# 1_Power.net
KiCad netlist of a schematic drawn in Altium Designer
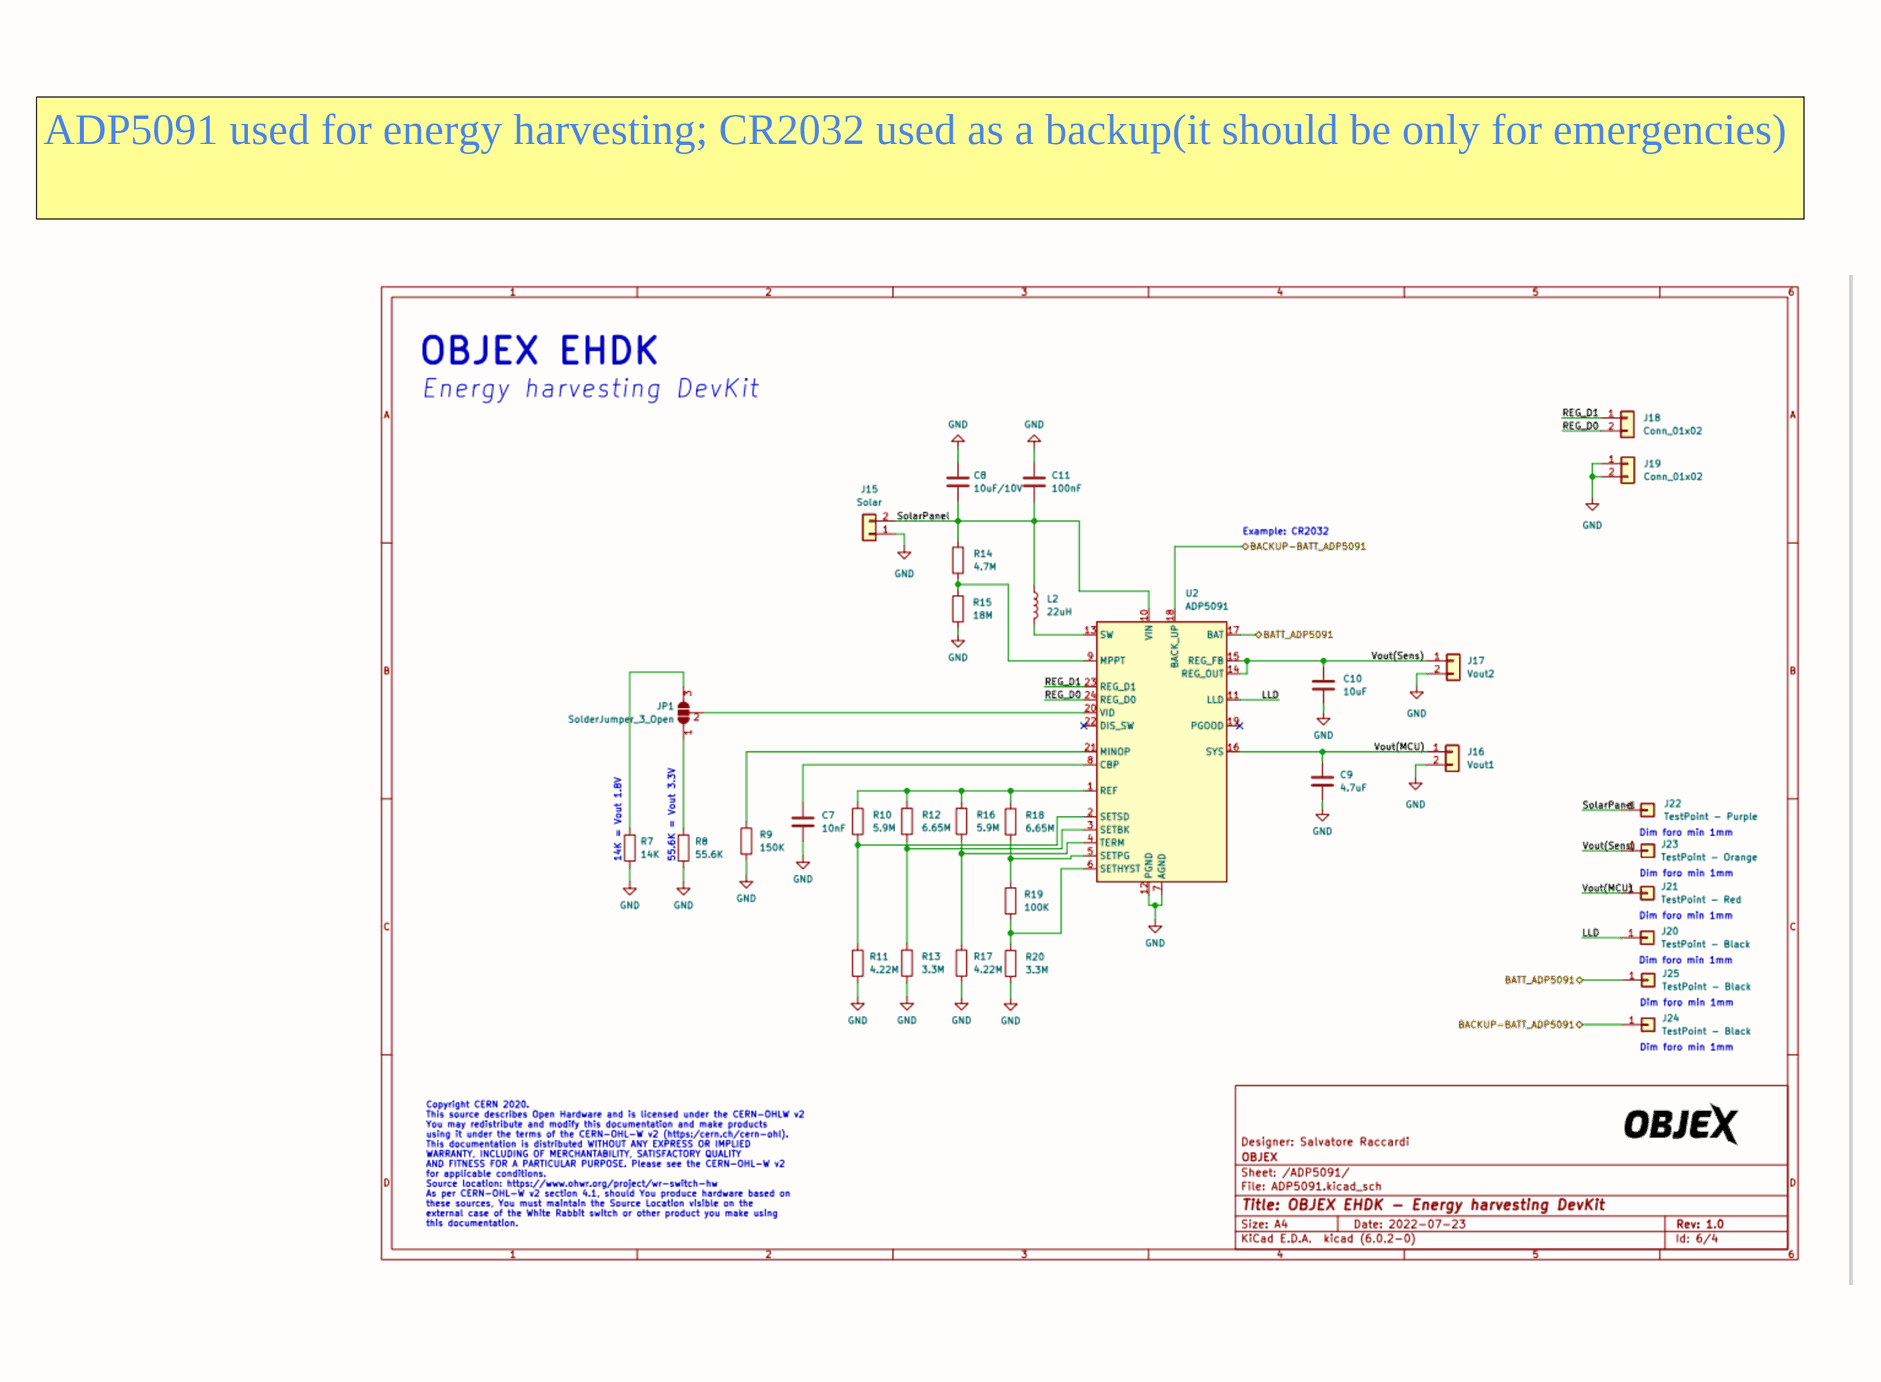
[diagram p0: 1_Power.SchDoc, left]
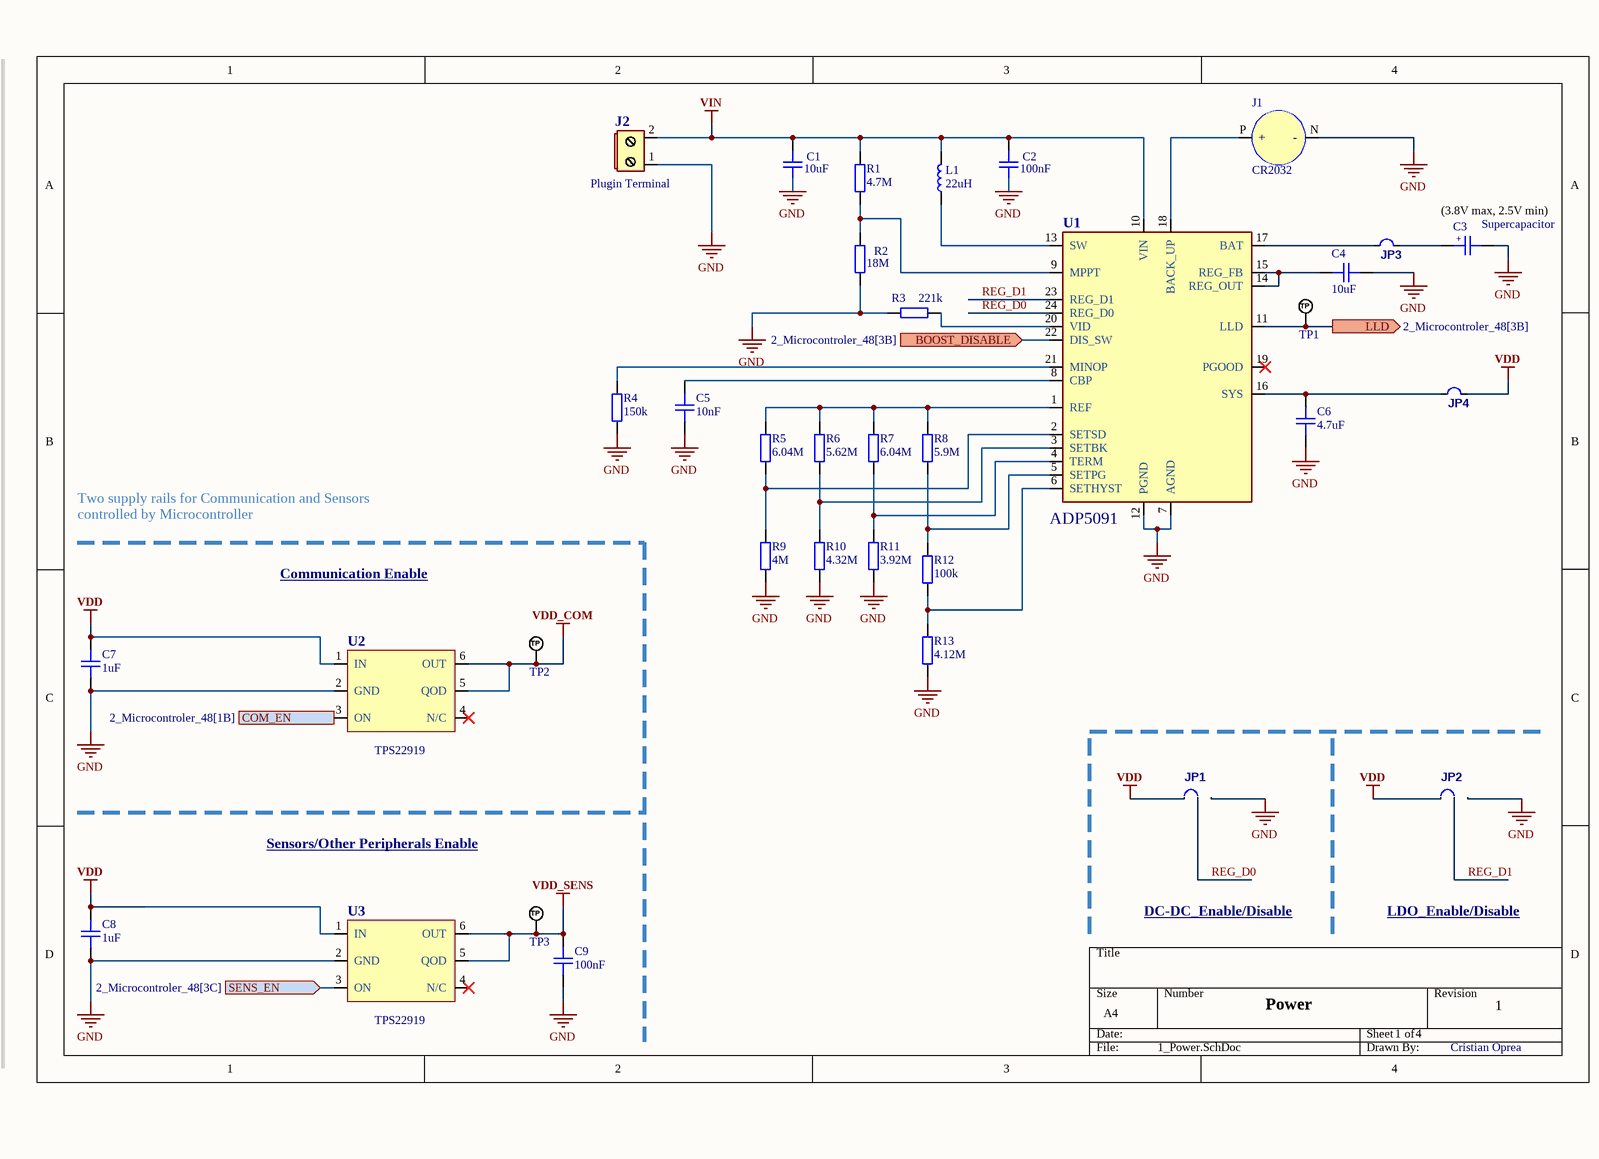
[diagram p1: 1_Power.SchDoc, middle]
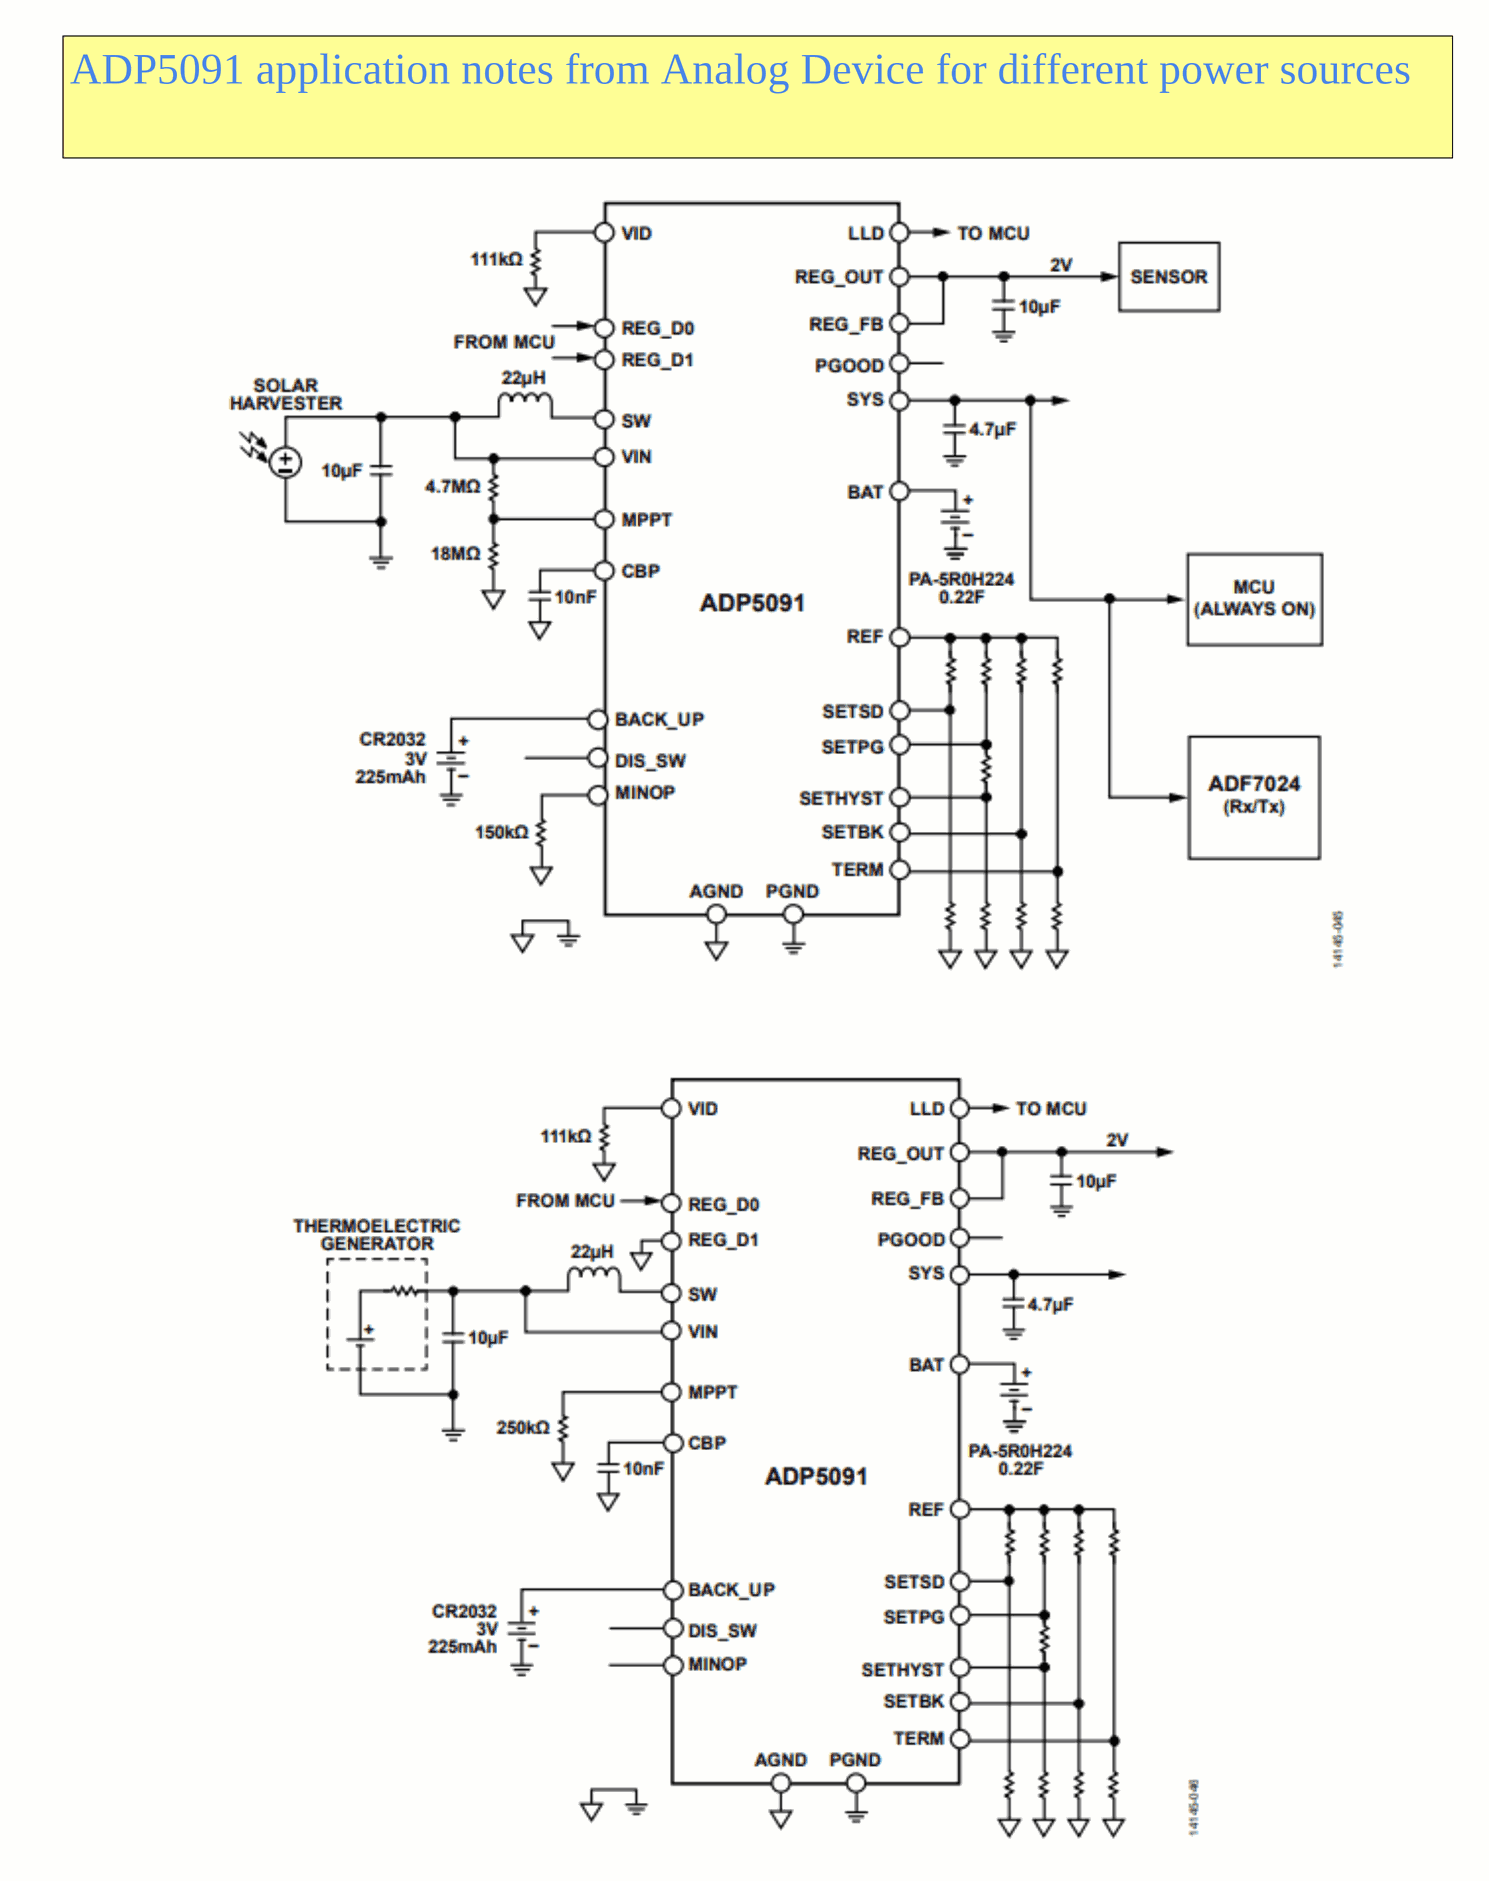
[diagram p2: 1_Power.SchDoc, right]

(export (version "E")
  (design (tool "Eeschema 10.0.6"))
  (components
    (comp (ref "C1")
      (value "10uF")
      (footprint "C0603")
      (description "Capacitor SMD 0603")
      (libsource (lib "Schlib_H2") (part "CAP_0603"))
    )
    (comp (ref "C2")
      (value "100nF")
      (footprint "C0603")
      (description "Capacitor SMD 0603")
      (libsource (lib "Schlib_H2") (part "CAP_0603"))
    )
    (comp (ref "C3")
      (value "Supercapacitor")
      (footprint "CAP_POL_8x16x3.5")
      (libsource (lib "Schlib_H2") (part "Supercapacitor"))
    )
    (comp (ref "C4")
      (value "10uF")
      (footprint "C0805")
      (description "Capacitor SMD 0805")
      (libsource (lib "Schlib_H2") (part "CAP_0805"))
    )
    (comp (ref "C5")
      (value "10nF")
      (footprint "C0603")
      (description "Capacitor SMD 0603")
      (libsource (lib "Schlib_H2") (part "CAP_0603"))
    )
    (comp (ref "C6")
      (value "4.7uF")
      (footprint "C0603")
      (description "Capacitor SMD 0603")
      (libsource (lib "Schlib_H2") (part "CAP_0603"))
    )
    (comp (ref "C7")
      (value "1uF")
      (footprint "C0603")
      (description "Capacitor SMD 0603")
      (libsource (lib "Schlib_H2") (part "CAP_0603"))
    )
    (comp (ref "C8")
      (value "1uF")
      (footprint "C0603")
      (description "Capacitor SMD 0603")
      (libsource (lib "Schlib_H2") (part "CAP_0603"))
    )
    (comp (ref "C9")
      (value "100nF")
      (footprint "C0603")
      (description "Capacitor SMD 0603")
      (libsource (lib "Schlib_H2") (part "CAP_0603"))
    )
    (comp (ref "J1")
      (value "CR2032")
      (footprint "BAT_CR2032-BS-6-1")
      (description "CR2032 Coin Cell Battery Holder")
      (fields (field (name "MANUFACTURER") "Q&J") (field (name "MANUFACTURER PART NUMBER") "CR2032-BS-6-1"))
      (libsource (lib "Schlib_H2") (part "CR2032-BS-6-1"))
    )
    (comp (ref "J2")
      (value "Plugin Terminal")
      (footprint "2.54_pluggable_terminal")
      (description "Screw terminal or plug terminal for power")
      (libsource (lib "Schlib_H2") (part "Power_Connector"))
    )
    (comp (ref "JP1")
      (value "JUMPER_3PIN")
      (footprint "HEADER_1x3_2.54")
      (libsource (lib "Schlib_H2") (part "JUMPER_3PIN"))
    )
    (comp (ref "JP2")
      (value "JUMPER_3PIN")
      (footprint "HEADER_1x3_2.54")
      (libsource (lib "Schlib_H2") (part "JUMPER_3PIN"))
    )
    (comp (ref "JP3")
      (value "JUMPER")
      (footprint "HEADER_1x2_2.54")
      (libsource (lib "Schlib_H2") (part "JUMPER"))
    )
    (comp (ref "JP4")
      (value "JUMPER")
      (footprint "HEADER_1x2_2.54")
      (libsource (lib "Schlib_H2") (part "JUMPER"))
    )
    (comp (ref "L1")
      (value "22uH")
      (footprint "IND_3.2_4")
      (description "Inductor SMD 1008")
      (libsource (lib "Schlib_H2") (part "IND_1008"))
    )
    (comp (ref "R1")
      (value "4.7M")
      (footprint "R0603")
      (description "Resistor SMD 0603")
      (libsource (lib "Schlib_H2") (part "RES_0603"))
    )
    (comp (ref "R2")
      (value "18M")
      (footprint "R0603")
      (description "Resistor SMD 0603")
      (libsource (lib "Schlib_H2") (part "RES_0603"))
    )
    (comp (ref "R3")
      (value "221k")
      (footprint "R0603")
      (description "Resistor SMD 0603")
      (libsource (lib "Schlib_H2") (part "RES_0603"))
    )
    (comp (ref "R4")
      (value "150k")
      (footprint "R0603")
      (description "Resistor SMD 0603")
      (libsource (lib "Schlib_H2") (part "RES_0603"))
    )
    (comp (ref "R5")
      (value "6.04M")
      (footprint "R0603")
      (description "Resistor SMD 0603")
      (libsource (lib "Schlib_H2") (part "RES_0603"))
    )
    (comp (ref "R6")
      (value "5.62M")
      (footprint "R0603")
      (description "Resistor SMD 0603")
      (libsource (lib "Schlib_H2") (part "RES_0603"))
    )
    (comp (ref "R7")
      (value "6.04M")
      (footprint "R0603")
      (description "Resistor SMD 0603")
      (libsource (lib "Schlib_H2") (part "RES_0603"))
    )
    (comp (ref "R8")
      (value "5.9M")
      (footprint "R0603")
      (description "Resistor SMD 0603")
      (libsource (lib "Schlib_H2") (part "RES_0603"))
    )
    (comp (ref "R9")
      (value "4M")
      (footprint "R0603")
      (description "Resistor SMD 0603")
      (libsource (lib "Schlib_H2") (part "RES_0603"))
    )
    (comp (ref "R10")
      (value "4.32M")
      (footprint "R0603")
      (description "Resistor SMD 0603")
      (libsource (lib "Schlib_H2") (part "RES_0603"))
    )
    (comp (ref "R11")
      (value "3.92M")
      (footprint "R0603")
      (description "Resistor SMD 0603")
      (libsource (lib "Schlib_H2") (part "RES_0603"))
    )
    (comp (ref "R12")
      (value "100k")
      (footprint "R0603")
      (description "Resistor SMD 0603")
      (libsource (lib "Schlib_H2") (part "RES_0603"))
    )
    (comp (ref "R13")
      (value "4.12M")
      (footprint "R0603")
      (description "Resistor SMD 0603")
      (libsource (lib "Schlib_H2") (part "RES_0603"))
    )
    (comp (ref "TP1")
      (value "TP_NOBOM")
      (footprint "TEST_PAD_THD")
      (description "Test Point Round 1mm (NO BOM)")
      (libsource (lib "Schlib_H2") (part "TEST_POINT_RND_1MM"))
    )
    (comp (ref "TP2")
      (value "TP_NOBOM")
      (footprint "TEST_PAD_THD")
      (description "Test Point Round 1mm (NO BOM)")
      (libsource (lib "Schlib_H2") (part "TEST_POINT_RND_1MM"))
    )
    (comp (ref "TP3")
      (value "TP_NOBOM")
      (footprint "TEST_PAD_THD")
      (description "Test Point Round 1mm (NO BOM)")
      (libsource (lib "Schlib_H2") (part "TEST_POINT_RND_1MM"))
    )
    (comp (ref "U1")
      (value "ADP5091")
      (footprint "LFCSP-24")
      (description "Ultralow Power Energy Harvester PMUs \r\nwith MPPT and Charge Management and BAckup Supply")
      (libsource (lib "Schlib_H2") (part "ADP5091"))
    )
    (comp (ref "U2")
      (value "TPS22919")
      (footprint "SC70-6")
      (description "5.5-V, 1.5-A, 90-mΩ load switch with adjustable output discharge")
      (libsource (lib "Schlib_H2") (part "TPS22919"))
    )
    (comp (ref "U3")
      (value "TPS22919")
      (footprint "SC70-6")
      (description "5.5-V, 1.5-A, 90-mΩ load switch with adjustable output discharge")
      (libsource (lib "Schlib_H2") (part "TPS22919"))
    )
  )
  (nets
    (net (code "1") (name "/BOOST_DISABLE") (class "Default")
      (node (ref "U1") (pin "22") (pinfunction "DIS_SW_22") (pintype "passive"))
    )
    (net (code "2") (name "/COM_EN") (class "Default")
      (node (ref "U2") (pin "3") (pinfunction "ON_3") (pintype "passive"))
    )
    (net (code "3") (name "/LLD") (class "Default")
      (node (ref "TP1") (pin "1") (pinfunction "TP_1") (pintype "passive"))
      (node (ref "U1") (pin "11") (pinfunction "LLD_11") (pintype "passive"))
    )
    (net (code "4") (name "/REG_D0") (class "Default")
      (node (ref "JP1") (pin "2") (pinfunction "2_2") (pintype "passive"))
      (node (ref "U1") (pin "24") (pinfunction "REG_D0_24") (pintype "passive"))
    )
    (net (code "5") (name "/REG_D1") (class "Default")
      (node (ref "JP2") (pin "2") (pinfunction "2_2") (pintype "passive"))
      (node (ref "U1") (pin "23") (pinfunction "REG_D1_23") (pintype "passive"))
    )
    (net (code "6") (name "/SENS_EN") (class "Default")
      (node (ref "U3") (pin "3") (pinfunction "ON_3") (pintype "passive"))
    )
    (net (code "7") (name "GND") (class "Default")
      (node (ref "C1") (pin "1") (pinfunction "1_1") (pintype "passive"))
      (node (ref "C2") (pin "1") (pinfunction "1_1") (pintype "passive"))
      (node (ref "C3") (pin "2") (pinfunction "2_2") (pintype "passive"))
      (node (ref "C4") (pin "2") (pinfunction "2_2") (pintype "passive"))
      (node (ref "C5") (pin "1") (pinfunction "1_1") (pintype "passive"))
      (node (ref "C6") (pin "1") (pinfunction "1_1") (pintype "passive"))
      (node (ref "C7") (pin "1") (pinfunction "1_1") (pintype "passive"))
      (node (ref "C8") (pin "1") (pinfunction "1_1") (pintype "passive"))
      (node (ref "C9") (pin "1") (pinfunction "1_1") (pintype "passive"))
      (node (ref "J1") (pin "N") (pinfunction "-_N") (pintype "passive"))
      (node (ref "J2") (pin "1") (pinfunction "1_1") (pintype "passive"))
      (node (ref "JP1") (pin "3") (pinfunction "3_3") (pintype "passive"))
      (node (ref "JP2") (pin "3") (pinfunction "3_3") (pintype "passive"))
      (node (ref "R10") (pin "1") (pinfunction "1_1") (pintype "passive"))
      (node (ref "R11") (pin "1") (pinfunction "1_1") (pintype "passive"))
      (node (ref "R13") (pin "1") (pinfunction "1_1") (pintype "passive"))
      (node (ref "R2") (pin "1") (pinfunction "1_1") (pintype "passive"))
      (node (ref "R3") (pin "1") (pinfunction "1_1") (pintype "passive"))
      (node (ref "R4") (pin "1") (pinfunction "1_1") (pintype "passive"))
      (node (ref "R9") (pin "1") (pinfunction "1_1") (pintype "passive"))
      (node (ref "U1") (pin "12") (pinfunction "PGND_12") (pintype "passive"))
      (node (ref "U1") (pin "7") (pinfunction "AGND_7") (pintype "passive"))
      (node (ref "U2") (pin "2") (pinfunction "GND_2") (pintype "passive"))
      (node (ref "U3") (pin "2") (pinfunction "GND_2") (pintype "passive"))
    )
    (net (code "8") (name "Net-(C3-Pad1)") (class "Default")
      (node (ref "C3") (pin "1") (pinfunction "1_1") (pintype "passive"))
      (node (ref "JP3") (pin "2") (pinfunction "2_2") (pintype "passive"))
    )
    (net (code "9") (name "Net-(J1-+)") (class "Default")
      (node (ref "J1") (pin "P") (pinfunction "+_P") (pintype "passive"))
      (node (ref "U1") (pin "18") (pinfunction "BACK_UP_18") (pintype "passive"))
    )
    (net (code "10") (name "Net-(U1-BAT)") (class "Default")
      (node (ref "JP3") (pin "1") (pinfunction "1_1") (pintype "passive"))
      (node (ref "U1") (pin "17") (pinfunction "BAT_17") (pintype "passive"))
    )
    (net (code "11") (name "Net-(U1-CBP)") (class "Default")
      (node (ref "C5") (pin "2") (pinfunction "2_2") (pintype "passive"))
      (node (ref "U1") (pin "8") (pinfunction "CBP_8") (pintype "passive"))
    )
    (net (code "12") (name "Net-(U1-MINOP)") (class "Default")
      (node (ref "R4") (pin "2") (pinfunction "2_2") (pintype "passive"))
      (node (ref "U1") (pin "21") (pinfunction "MINOP_21") (pintype "passive"))
    )
    (net (code "13") (name "Net-(U1-MPPT)") (class "Default")
      (node (ref "R1") (pin "1") (pinfunction "1_1") (pintype "passive"))
      (node (ref "R2") (pin "2") (pinfunction "2_2") (pintype "passive"))
      (node (ref "U1") (pin "9") (pinfunction "MPPT_9") (pintype "passive"))
    )
    (net (code "14") (name "Net-(U1-REF)") (class "Default")
      (node (ref "R5") (pin "2") (pinfunction "2_2") (pintype "passive"))
      (node (ref "R6") (pin "2") (pinfunction "2_2") (pintype "passive"))
      (node (ref "R7") (pin "2") (pinfunction "2_2") (pintype "passive"))
      (node (ref "R8") (pin "2") (pinfunction "2_2") (pintype "passive"))
      (node (ref "U1") (pin "1") (pinfunction "REF_1") (pintype "passive"))
    )
    (net (code "15") (name "Net-(U1-REG_FB)") (class "Default")
      (node (ref "C4") (pin "1") (pinfunction "1_1") (pintype "passive"))
      (node (ref "U1") (pin "14") (pinfunction "REG_OUT_14") (pintype "passive"))
      (node (ref "U1") (pin "15") (pinfunction "REG_FB_15") (pintype "passive"))
    )
    (net (code "16") (name "Net-(U1-SETBK)") (class "Default")
      (node (ref "R10") (pin "2") (pinfunction "2_2") (pintype "passive"))
      (node (ref "R6") (pin "1") (pinfunction "1_1") (pintype "passive"))
      (node (ref "U1") (pin "3") (pinfunction "SETBK_3") (pintype "passive"))
    )
    (net (code "17") (name "Net-(U1-SETHYST)") (class "Default")
      (node (ref "R12") (pin "1") (pinfunction "1_1") (pintype "passive"))
      (node (ref "R13") (pin "2") (pinfunction "2_2") (pintype "passive"))
      (node (ref "U1") (pin "6") (pinfunction "SETHYST_6") (pintype "passive"))
    )
    (net (code "18") (name "Net-(U1-SETPG)") (class "Default")
      (node (ref "R12") (pin "2") (pinfunction "2_2") (pintype "passive"))
      (node (ref "R8") (pin "1") (pinfunction "1_1") (pintype "passive"))
      (node (ref "U1") (pin "5") (pinfunction "SETPG_5") (pintype "passive"))
    )
    (net (code "19") (name "Net-(U1-SETSD)") (class "Default")
      (node (ref "R5") (pin "1") (pinfunction "1_1") (pintype "passive"))
      (node (ref "R9") (pin "2") (pinfunction "2_2") (pintype "passive"))
      (node (ref "U1") (pin "2") (pinfunction "SETSD_2") (pintype "passive"))
    )
    (net (code "20") (name "Net-(U1-SW)") (class "Default")
      (node (ref "L1") (pin "1") (pinfunction "1_1") (pintype "passive"))
      (node (ref "U1") (pin "13") (pinfunction "SW_13") (pintype "passive"))
    )
    (net (code "21") (name "Net-(U1-SYS)") (class "Default")
      (node (ref "C6") (pin "2") (pinfunction "2_2") (pintype "passive"))
      (node (ref "JP4") (pin "1") (pinfunction "1_1") (pintype "passive"))
      (node (ref "U1") (pin "16") (pinfunction "SYS_16") (pintype "passive"))
    )
    (net (code "22") (name "Net-(U1-TERM)") (class "Default")
      (node (ref "R11") (pin "2") (pinfunction "2_2") (pintype "passive"))
      (node (ref "R7") (pin "1") (pinfunction "1_1") (pintype "passive"))
      (node (ref "U1") (pin "4") (pinfunction "TERM_4") (pintype "passive"))
    )
    (net (code "23") (name "Net-(U1-VID)") (class "Default")
      (node (ref "R3") (pin "2") (pinfunction "2_2") (pintype "passive"))
      (node (ref "U1") (pin "20") (pinfunction "VID_20") (pintype "passive"))
    )
    (net (code "24") (name "VDD") (class "Default")
      (node (ref "C7") (pin "2") (pinfunction "2_2") (pintype "passive"))
      (node (ref "C8") (pin "2") (pinfunction "2_2") (pintype "passive"))
      (node (ref "JP1") (pin "1") (pinfunction "1_1") (pintype "passive"))
      (node (ref "JP2") (pin "1") (pinfunction "1_1") (pintype "passive"))
      (node (ref "JP4") (pin "2") (pinfunction "2_2") (pintype "passive"))
      (node (ref "U2") (pin "1") (pinfunction "IN_1") (pintype "passive"))
      (node (ref "U3") (pin "1") (pinfunction "IN_1") (pintype "passive"))
    )
    (net (code "25") (name "VDD_COM") (class "Default")
      (node (ref "TP2") (pin "1") (pinfunction "TP_1") (pintype "passive"))
      (node (ref "U2") (pin "5") (pinfunction "QOD_5") (pintype "passive"))
      (node (ref "U2") (pin "6") (pinfunction "OUT_6") (pintype "passive"))
    )
    (net (code "26") (name "VDD_SENS") (class "Default")
      (node (ref "C9") (pin "2") (pinfunction "2_2") (pintype "passive"))
      (node (ref "TP3") (pin "1") (pinfunction "TP_1") (pintype "passive"))
      (node (ref "U3") (pin "5") (pinfunction "QOD_5") (pintype "passive"))
      (node (ref "U3") (pin "6") (pinfunction "OUT_6") (pintype "passive"))
    )
    (net (code "27") (name "VIN") (class "Default")
      (node (ref "C1") (pin "2") (pinfunction "2_2") (pintype "passive"))
      (node (ref "C2") (pin "2") (pinfunction "2_2") (pintype "passive"))
      (node (ref "J2") (pin "2") (pinfunction "2_2") (pintype "passive"))
      (node (ref "L1") (pin "2") (pinfunction "2_2") (pintype "passive"))
      (node (ref "R1") (pin "2") (pinfunction "2_2") (pintype "passive"))
      (node (ref "U1") (pin "10") (pinfunction "VIN_10") (pintype "passive"))
    )
    (net (code "28") (name "unconnected-(U1-PGOOD-Pad19)") (class "Default")
      (node (ref "U1") (pin "19") (pinfunction "PGOOD_19") (pintype "passive+no_connect"))
    )
    (net (code "29") (name "unconnected-(U2-N{slash}C-Pad4)") (class "Default")
      (node (ref "U2") (pin "4") (pinfunction "N/C_4") (pintype "passive+no_connect"))
    )
    (net (code "30") (name "unconnected-(U3-N{slash}C-Pad4)") (class "Default")
      (node (ref "U3") (pin "4") (pinfunction "N/C_4") (pintype "passive+no_connect"))
    )
  )
)
